# schematic.net
KiCad netlist of a schematic drawn in EasyEDA
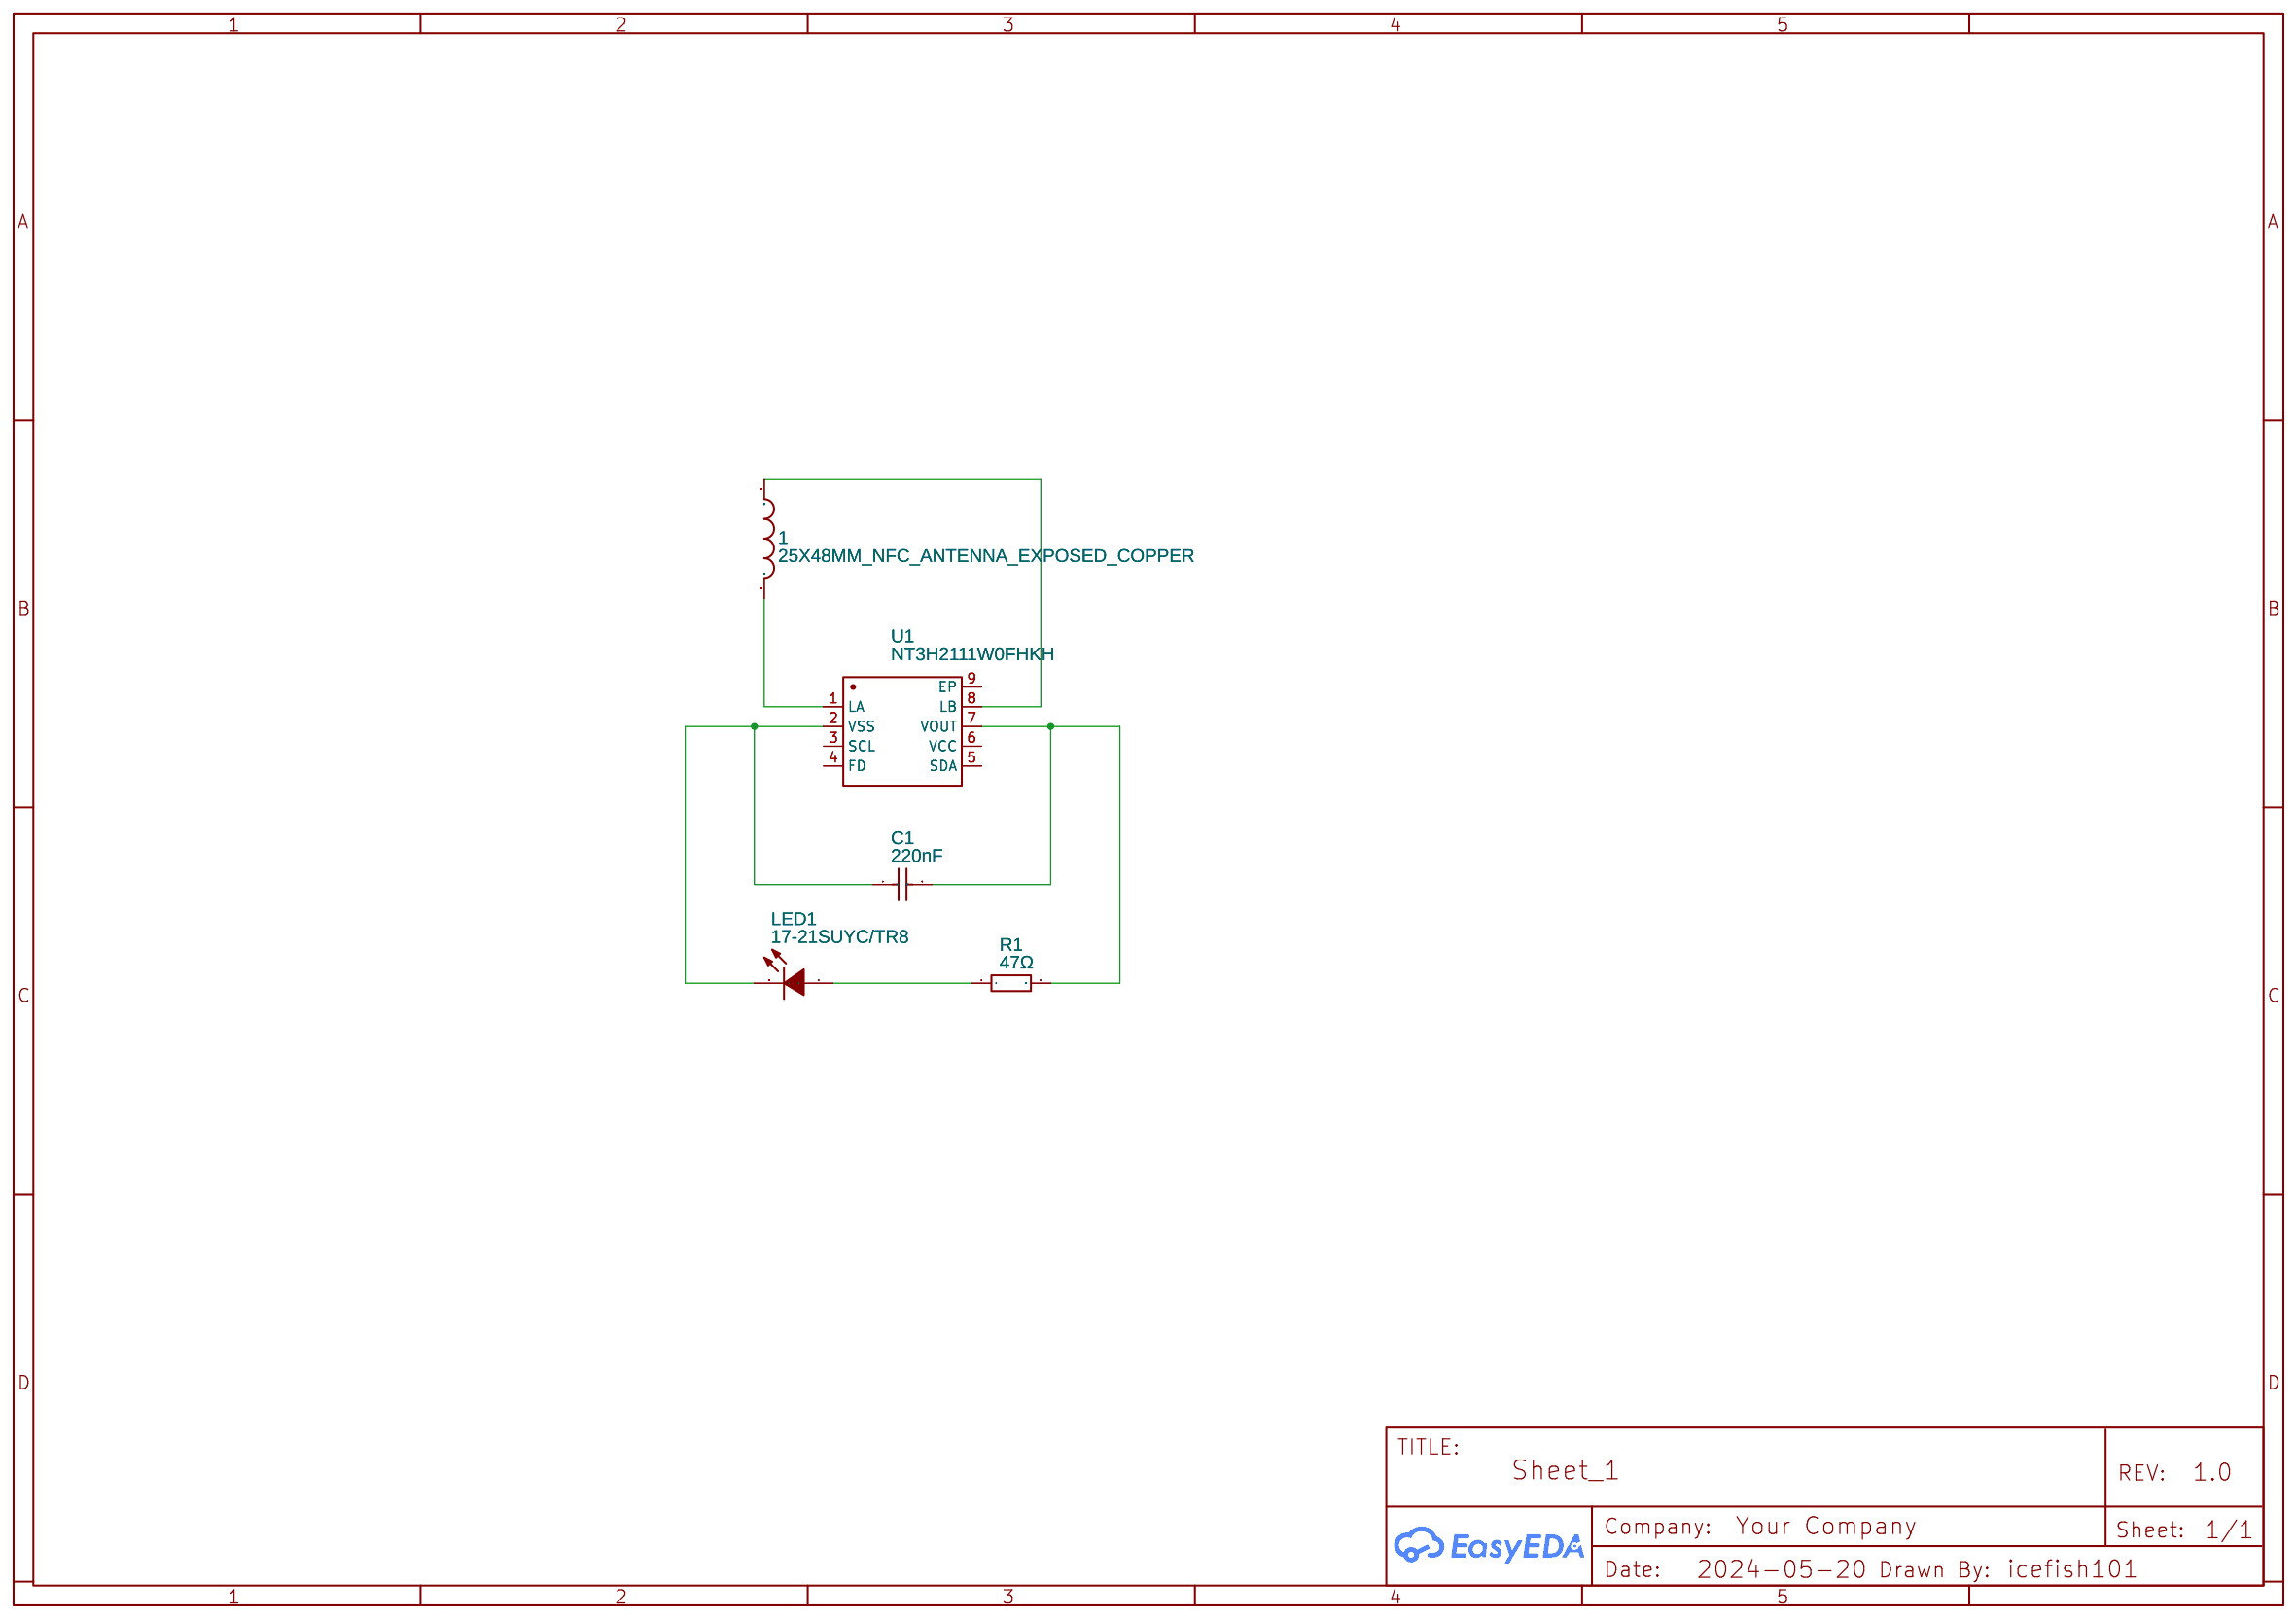
[diagram p0: schematic sheet]

(export (version "E")
  (design (tool "Eeschema 10.0.6"))
  (components
    (comp (ref "1")
      (value "25X48MM_NFC_ANTENNA_EXPOSED_COPPER")
      (libsource (lib "") (part "25X48MM_NFC_ANTENNA_EXPOSED_COPPER"))
    )
    (comp (ref "C1")
      (value "220nF")
      (fields
        (field (name "Manufacturer Part") "CL10B224KA8NNNC")
        (field (name "Manufacturer") "SAMSUNG(三星)")
      )
      (libsource (lib "") (part "CL10B224KA8NNNC"))
    )
    (comp (ref "LED1")
      (value "17-21SUYC/TR8")
      (fields (field (name "Manufacturer Part") "KT-0805黄灯") (field (name "Manufacturer") "KENTO"))
      (libsource (lib "") (part "17-21SUYC/TR8"))
    )
    (comp (ref "R1")
      (value "47Ω")
      (fields
        (field (name "Manufacturer Part") "0603WAF470JT5E")
        (field (name "Manufacturer") "UNI-ROYAL(厚声)")
      )
      (libsource (lib "") (part "0603WAF470JT5E"))
    )
    (comp (ref "U1")
      (value "NT3H2111W0FHKH")
      (fields (field (name "Manufacturer") "NXP(恩智浦)"))
      (libsource (lib "") (part "NT3H2111W0FHKH"))
    )
  )
  (nets
    (net (code "1") (name "Net-(LED1-+)") (class "Default")
      (node (ref "LED1") (pin "1") (pinfunction "+_1") (pintype "unspecified"))
      (node (ref "R1") (pin "1") (pinfunction "1_1") (pintype "input"))
    )
    (net (code "2") (name "Net-(LED1--)") (class "Default")
      (node (ref "C1") (pin "1") (pinfunction "1_1") (pintype "input"))
      (node (ref "LED1") (pin "2") (pinfunction "-_2") (pintype "unspecified"))
      (node (ref "U1") (pin "2") (pinfunction "VSS_2") (pintype "unspecified"))
    )
    (net (code "3") (name "Net-(U1-LA)") (class "Default")
      (node (ref "1") (pin "P$2") (pinfunction "P$2_P$2") (pintype "bidirectional"))
      (node (ref "U1") (pin "1") (pinfunction "LA_1") (pintype "unspecified"))
    )
    (net (code "4") (name "Net-(U1-LB)") (class "Default")
      (node (ref "1") (pin "P$1") (pinfunction "P$1_P$1") (pintype "bidirectional"))
      (node (ref "U1") (pin "8") (pinfunction "LB_8") (pintype "unspecified"))
    )
    (net (code "5") (name "Net-(U1-VOUT)") (class "Default")
      (node (ref "C1") (pin "2") (pinfunction "2_2") (pintype "input"))
      (node (ref "R1") (pin "2") (pinfunction "2_2") (pintype "input"))
      (node (ref "U1") (pin "7") (pinfunction "VOUT_7") (pintype "unspecified"))
    )
    (net (code "6") (name "unconnected-(U1-EP-Pad9)") (class "Default")
      (node (ref "U1") (pin "9") (pinfunction "EP_9") (pintype "unspecified"))
    )
    (net (code "7") (name "unconnected-(U1-FD-Pad4)") (class "Default")
      (node (ref "U1") (pin "4") (pinfunction "FD_4") (pintype "unspecified"))
    )
    (net (code "8") (name "unconnected-(U1-SCL-Pad3)") (class "Default")
      (node (ref "U1") (pin "3") (pinfunction "SCL_3") (pintype "unspecified"))
    )
    (net (code "9") (name "unconnected-(U1-SDA-Pad5)") (class "Default")
      (node (ref "U1") (pin "5") (pinfunction "SDA_5") (pintype "unspecified"))
    )
    (net (code "10") (name "unconnected-(U1-VCC-Pad6)") (class "Default")
      (node (ref "U1") (pin "6") (pinfunction "VCC_6") (pintype "unspecified"))
    )
  )
)
